# AnalogSigCond.net
KiCad netlist of a schematic drawn in Altium Designer
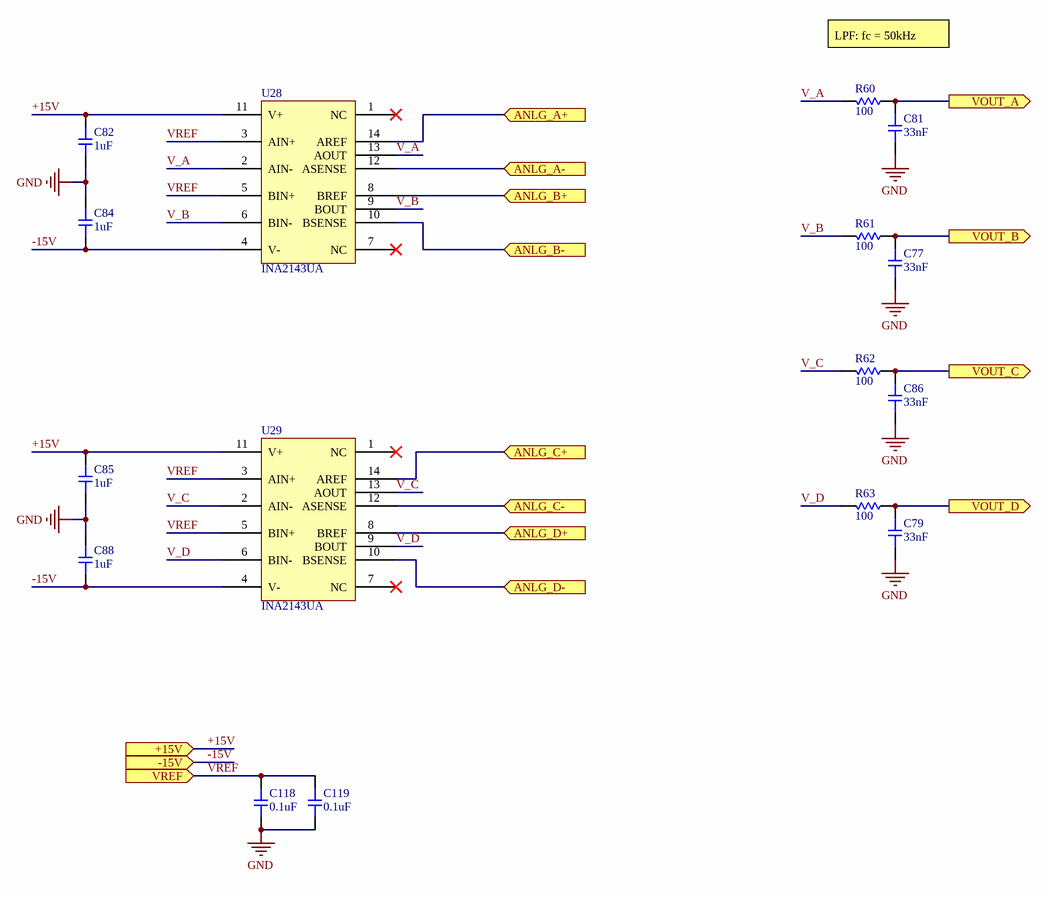
[diagram p0: AnalogSigCond.SchDoc]

(export (version "E")
  (design (tool "Eeschema 10.0.6"))
  (components
    (comp (ref "C77")
      (value "33nF")
      (footprint "0603-CAP")
      (description "Capacitor")
      (libsource (lib "AMDC") (part "Capacitor"))
    )
    (comp (ref "C79")
      (value "33nF")
      (footprint "0603-CAP")
      (description "Capacitor")
      (libsource (lib "AMDC") (part "Capacitor"))
    )
    (comp (ref "C81")
      (value "33nF")
      (footprint "0603-CAP")
      (description "Capacitor")
      (libsource (lib "AMDC") (part "Capacitor"))
    )
    (comp (ref "C82")
      (value "1uF")
      (footprint "0603-CAP")
      (description "Capacitor")
      (libsource (lib "AMDC") (part "Capacitor"))
    )
    (comp (ref "C84")
      (value "1uF")
      (footprint "0603-CAP")
      (description "Capacitor")
      (libsource (lib "AMDC") (part "Capacitor"))
    )
    (comp (ref "C85")
      (value "1uF")
      (footprint "0603-CAP")
      (description "Capacitor")
      (libsource (lib "AMDC") (part "Capacitor"))
    )
    (comp (ref "C86")
      (value "33nF")
      (footprint "0603-CAP")
      (description "Capacitor")
      (libsource (lib "AMDC") (part "Capacitor"))
    )
    (comp (ref "C88")
      (value "1uF")
      (footprint "0603-CAP")
      (description "Capacitor")
      (libsource (lib "AMDC") (part "Capacitor"))
    )
    (comp (ref "C118")
      (value "0.1uF")
      (footprint "0603-CAP")
      (description "Capacitor")
      (libsource (lib "AMDC") (part "Capacitor"))
    )
    (comp (ref "C119")
      (value "0.1uF")
      (footprint "0603-CAP")
      (description "Capacitor")
      (libsource (lib "AMDC") (part "Capacitor"))
    )
    (comp (ref "R60")
      (value "100")
      (footprint "0603-RES")
      (description "Resistor")
      (libsource (lib "AMDC") (part "Resistor"))
    )
    (comp (ref "R61")
      (value "100")
      (footprint "0603-RES")
      (description "Resistor")
      (libsource (lib "AMDC") (part "Resistor"))
    )
    (comp (ref "R62")
      (value "100")
      (footprint "0603-RES")
      (description "Resistor")
      (libsource (lib "AMDC") (part "Resistor"))
    )
    (comp (ref "R63")
      (value "100")
      (footprint "0603-RES")
      (description "Resistor")
      (libsource (lib "AMDC") (part "Resistor"))
    )
    (comp (ref "U28")
      (value "INA2143UA")
      (footprint "SOIC127P600X175-14N")
      (description "IC OPAMP DIFF 150KHZ 14SOIC")
      (libsource (lib "AMDC") (part "INA2143UA"))
    )
    (comp (ref "U29")
      (value "INA2143UA")
      (footprint "SOIC127P600X175-14N")
      (description "IC OPAMP DIFF 150KHZ 14SOIC")
      (libsource (lib "AMDC") (part "INA2143UA"))
    )
  )
  (nets
    (net (code "1") (name "/+15V") (class "Default")
      (node (ref "C82") (pin "2") (pinfunction "2_2") (pintype "passive"))
      (node (ref "C85") (pin "2") (pinfunction "2_2") (pintype "passive"))
      (node (ref "U28") (pin "11") (pinfunction "V+_11") (pintype "passive"))
      (node (ref "U29") (pin "11") (pinfunction "V+_11") (pintype "passive"))
    )
    (net (code "2") (name "/-15V") (class "Default")
      (node (ref "C84") (pin "1") (pinfunction "1_1") (pintype "passive"))
      (node (ref "C88") (pin "1") (pinfunction "1_1") (pintype "passive"))
      (node (ref "U28") (pin "4") (pinfunction "V-_4") (pintype "passive"))
      (node (ref "U29") (pin "4") (pinfunction "V-_4") (pintype "passive"))
    )
    (net (code "3") (name "/ANLG_A+") (class "Default")
      (node (ref "U28") (pin "14") (pinfunction "AREF_14") (pintype "passive"))
    )
    (net (code "4") (name "/ANLG_A-") (class "Default")
      (node (ref "U28") (pin "12") (pinfunction "ASENSE_12") (pintype "passive"))
    )
    (net (code "5") (name "/ANLG_B+") (class "Default")
      (node (ref "U28") (pin "8") (pinfunction "BREF_8") (pintype "passive"))
    )
    (net (code "6") (name "/ANLG_B-") (class "Default")
      (node (ref "U28") (pin "10") (pinfunction "BSENSE_10") (pintype "passive"))
    )
    (net (code "7") (name "/ANLG_C+") (class "Default")
      (node (ref "U29") (pin "14") (pinfunction "AREF_14") (pintype "passive"))
    )
    (net (code "8") (name "/ANLG_C-") (class "Default")
      (node (ref "U29") (pin "12") (pinfunction "ASENSE_12") (pintype "passive"))
    )
    (net (code "9") (name "/ANLG_D+") (class "Default")
      (node (ref "U29") (pin "8") (pinfunction "BREF_8") (pintype "passive"))
    )
    (net (code "10") (name "/ANLG_D-") (class "Default")
      (node (ref "U29") (pin "10") (pinfunction "BSENSE_10") (pintype "passive"))
    )
    (net (code "11") (name "/VOUT_A") (class "Default")
      (node (ref "C81") (pin "1") (pinfunction "1_1") (pintype "passive"))
      (node (ref "R60") (pin "1") (pinfunction "1_1") (pintype "passive"))
    )
    (net (code "12") (name "/VOUT_B") (class "Default")
      (node (ref "C77") (pin "1") (pinfunction "1_1") (pintype "passive"))
      (node (ref "R61") (pin "1") (pinfunction "1_1") (pintype "passive"))
    )
    (net (code "13") (name "/VOUT_C") (class "Default")
      (node (ref "C86") (pin "1") (pinfunction "1_1") (pintype "passive"))
      (node (ref "R62") (pin "1") (pinfunction "1_1") (pintype "passive"))
    )
    (net (code "14") (name "/VOUT_D") (class "Default")
      (node (ref "C79") (pin "1") (pinfunction "1_1") (pintype "passive"))
      (node (ref "R63") (pin "1") (pinfunction "1_1") (pintype "passive"))
    )
    (net (code "15") (name "/VREF") (class "Default")
      (node (ref "C118") (pin "1") (pinfunction "1_1") (pintype "passive"))
      (node (ref "C119") (pin "1") (pinfunction "1_1") (pintype "passive"))
      (node (ref "U28") (pin "3") (pinfunction "AIN+_3") (pintype "passive"))
      (node (ref "U28") (pin "5") (pinfunction "BIN+_5") (pintype "passive"))
      (node (ref "U29") (pin "3") (pinfunction "AIN+_3") (pintype "passive"))
      (node (ref "U29") (pin "5") (pinfunction "BIN+_5") (pintype "passive"))
    )
    (net (code "16") (name "/V_A") (class "Default")
      (node (ref "R60") (pin "2") (pinfunction "2_2") (pintype "passive"))
      (node (ref "U28") (pin "13") (pinfunction "AOUT_13") (pintype "passive"))
      (node (ref "U28") (pin "2") (pinfunction "AIN-_2") (pintype "passive"))
    )
    (net (code "17") (name "/V_B") (class "Default")
      (node (ref "R61") (pin "2") (pinfunction "2_2") (pintype "passive"))
      (node (ref "U28") (pin "6") (pinfunction "BIN-_6") (pintype "passive"))
      (node (ref "U28") (pin "9") (pinfunction "BOUT_9") (pintype "passive"))
    )
    (net (code "18") (name "/V_C") (class "Default")
      (node (ref "R62") (pin "2") (pinfunction "2_2") (pintype "passive"))
      (node (ref "U29") (pin "13") (pinfunction "AOUT_13") (pintype "passive"))
      (node (ref "U29") (pin "2") (pinfunction "AIN-_2") (pintype "passive"))
    )
    (net (code "19") (name "/V_D") (class "Default")
      (node (ref "R63") (pin "2") (pinfunction "2_2") (pintype "passive"))
      (node (ref "U29") (pin "6") (pinfunction "BIN-_6") (pintype "passive"))
      (node (ref "U29") (pin "9") (pinfunction "BOUT_9") (pintype "passive"))
    )
    (net (code "20") (name "GND") (class "Default")
      (node (ref "C118") (pin "2") (pinfunction "2_2") (pintype "passive"))
      (node (ref "C119") (pin "2") (pinfunction "2_2") (pintype "passive"))
      (node (ref "C77") (pin "2") (pinfunction "2_2") (pintype "passive"))
      (node (ref "C79") (pin "2") (pinfunction "2_2") (pintype "passive"))
      (node (ref "C81") (pin "2") (pinfunction "2_2") (pintype "passive"))
      (node (ref "C82") (pin "1") (pinfunction "1_1") (pintype "passive"))
      (node (ref "C84") (pin "2") (pinfunction "2_2") (pintype "passive"))
      (node (ref "C85") (pin "1") (pinfunction "1_1") (pintype "passive"))
      (node (ref "C86") (pin "2") (pinfunction "2_2") (pintype "passive"))
      (node (ref "C88") (pin "2") (pinfunction "2_2") (pintype "passive"))
    )
    (net (code "21") (name "unconnected-(U28-NC-Pad1)") (class "Default")
      (node (ref "U28") (pin "1") (pinfunction "NC_1") (pintype "passive+no_connect"))
    )
    (net (code "22") (name "unconnected-(U28-NC-Pad7)") (class "Default")
      (node (ref "U28") (pin "7") (pinfunction "NC_7") (pintype "passive+no_connect"))
    )
    (net (code "23") (name "unconnected-(U29-NC-Pad1)") (class "Default")
      (node (ref "U29") (pin "1") (pinfunction "NC_1") (pintype "passive+no_connect"))
    )
    (net (code "24") (name "unconnected-(U29-NC-Pad7)") (class "Default")
      (node (ref "U29") (pin "7") (pinfunction "NC_7") (pintype "passive+no_connect"))
    )
  )
)
